# KNoT_Thing_Starter2_Board.net
KiCad netlist of a schematic drawn in Altium Designer
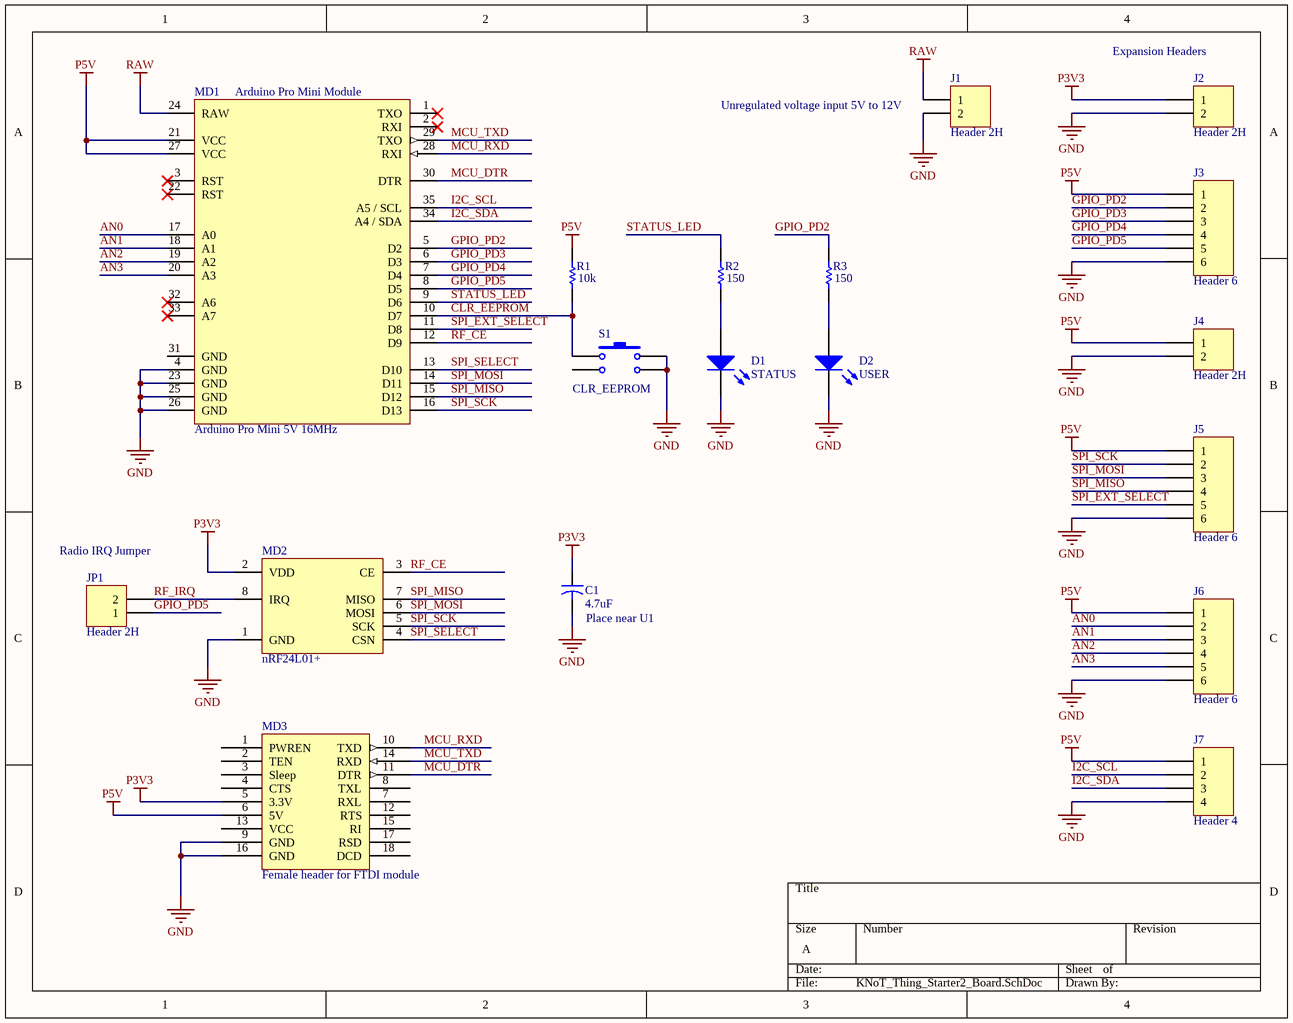
[diagram p0: KNoT_Thing_Starter2_Board.SchDoc]

(export (version "E")
  (design (tool "Eeschema 10.0.6"))
  (components
    (comp (ref "C1")
      (value "4.7uF")
      (footprint "CAP RADIAL 5mm")
      (description "Capacitor Radial 4.7µF")
      (fields (field (name "Comment") "CAPC_RADIAL_100") (field (name "PUBLISHER") "Altium Limited"))
      (libsource (lib "KNoT_Thing") (part "CAPC1608L_1"))
    )
    (comp (ref "D1")
      (value "STATUS")
      (footprint "LED")
      (description "Typical RED, GREEN, YELLOW, AMBER GaAs LED")
      (fields (field (name "PUBLISHER") "Altium Limited"))
      (libsource (lib "KNoT_Thing") (part "LED"))
    )
    (comp (ref "D2")
      (value "USER")
      (footprint "LED")
      (description "Typical RED, GREEN, YELLOW, AMBER GaAs LED")
      (fields (field (name "PUBLISHER") "Altium Limited"))
      (libsource (lib "KNoT_Thing") (part "LED"))
    )
    (comp (ref "J1")
      (value "Header 2H")
      (footprint "HDR1X2")
      (description "Header, 2-Pin, Right Angle")
      (fields (field (name "PUBLISHER") "Altium Limited"))
      (libsource (lib "KNoT_Thing") (part "Header 2H"))
    )
    (comp (ref "J2")
      (value "Header 2H")
      (footprint "HDR1X2")
      (description "Header, 2-Pin, Right Angle")
      (fields (field (name "PUBLISHER") "Altium Limited"))
      (libsource (lib "KNoT_Thing") (part "Header 2H"))
    )
    (comp (ref "J3")
      (value "Header 6")
      (footprint "HDR1X6")
      (description "Header, 6-Pin")
      (fields (field (name "PUBLISHER") "Altium Limited"))
      (libsource (lib "KNoT_Thing") (part "Header 6"))
    )
    (comp (ref "J4")
      (value "Header 2H")
      (footprint "HDR1X2")
      (description "Header, 2-Pin, Right Angle")
      (fields (field (name "PUBLISHER") "Altium Limited"))
      (libsource (lib "KNoT_Thing") (part "Header 2H"))
    )
    (comp (ref "J5")
      (value "Header 6")
      (footprint "HDR1X6")
      (description "Header, 6-Pin")
      (fields (field (name "PUBLISHER") "Altium Limited"))
      (libsource (lib "KNoT_Thing") (part "Header 6"))
    )
    (comp (ref "J6")
      (value "Header 6")
      (footprint "HDR1X6")
      (description "Header, 6-Pin")
      (fields (field (name "PUBLISHER") "Altium Limited"))
      (libsource (lib "KNoT_Thing") (part "Header 6"))
    )
    (comp (ref "J7")
      (value "Header 4")
      (footprint "HDR1X4")
      (description "Header, 4-Pin")
      (fields (field (name "PUBLISHER") "Altium Limited"))
      (libsource (lib "KNoT_Thing") (part "Header 4"))
    )
    (comp (ref "JP1")
      (value "Header 2H")
      (footprint "HDR1X2")
      (description "Header, 2-Pin, Right Angle")
      (fields (field (name "PUBLISHER") "Altium Limited"))
      (libsource (lib "") (part "Header 2H_1"))
    )
    (comp (ref "MD1")
      (value "Arduino Pro Mini 5V 16MHz")
      (footprint "Arduino Pro Mini")
      (libsource (lib "KNoT_Thing") (part "Arduino Pro Mini 5V 16MHz"))
    )
    (comp (ref "MD2")
      (value "nRF24L01+")
      (footprint "nRF24L01+ Module")
      (description "2x4 Female Header Conector")
      (libsource (lib "KNoT_Thing") (part "nRF24L01+ Module"))
    )
    (comp (ref "MD3")
      (value "Female header for FTDI module")
      (footprint "FTDI_Module")
      (description "Connection header for custom FTDI module")
      (libsource (lib "KNoT_Thing") (part "Module_FTDI"))
    )
    (comp (ref "R1")
      (value "10k")
      (footprint "AXIAL-3mm")
      (description "Resistor")
      (fields (field (name "Comment") "Res1") (field (name "PUBLISHER") "Altium Limited"))
      (libsource (lib "KNoT_Thing") (part "Res1"))
    )
    (comp (ref "R2")
      (value "150")
      (footprint "AXIAL-3mm")
      (description "Resistor")
      (fields (field (name "Comment") "Res1") (field (name "PUBLISHER") "Altium Limited"))
      (libsource (lib "KNoT_Thing") (part "Res1"))
    )
    (comp (ref "R3")
      (value "150")
      (footprint "AXIAL-3mm")
      (description "Resistor")
      (fields (field (name "Comment") "Res1") (field (name "PUBLISHER") "Altium Limited"))
      (libsource (lib "KNoT_Thing") (part "Res1"))
    )
    (comp (ref "S1")
      (value "CLR_EEPROM")
      (footprint "SW-TACT")
      (description "B3F-1002 SWITCH TACT 6MM MOM 150GF")
      (fields (field (name "PUBLISHER") "Altium Limited"))
      (libsource (lib "KNoT_Thing") (part "SW-PB"))
    )
  )
  (nets
    (net (code "1") (name "/AN0") (class "Default")
      (node (ref "J6") (pin "2") (pinfunction "2_2") (pintype "passive"))
      (node (ref "MD1") (pin "17") (pinfunction "A0_17") (pintype "passive"))
    )
    (net (code "2") (name "/AN1") (class "Default")
      (node (ref "J6") (pin "3") (pinfunction "3_3") (pintype "passive"))
      (node (ref "MD1") (pin "18") (pinfunction "A1_18") (pintype "passive"))
    )
    (net (code "3") (name "/AN2") (class "Default")
      (node (ref "J6") (pin "4") (pinfunction "4_4") (pintype "passive"))
      (node (ref "MD1") (pin "19") (pinfunction "A2_19") (pintype "passive"))
    )
    (net (code "4") (name "/AN3") (class "Default")
      (node (ref "J6") (pin "5") (pinfunction "5_5") (pintype "passive"))
      (node (ref "MD1") (pin "20") (pinfunction "A3_20") (pintype "passive"))
    )
    (net (code "5") (name "/CLR_EEPROM") (class "Default")
      (node (ref "MD1") (pin "10") (pinfunction "D7_10") (pintype "passive"))
      (node (ref "R1") (pin "2") (pinfunction "2_2") (pintype "passive"))
      (node (ref "S1") (pin "1") (pinfunction "1_1") (pintype "passive"))
    )
    (net (code "6") (name "/GPIO_PD2") (class "Default")
      (node (ref "J3") (pin "2") (pinfunction "2_2") (pintype "passive"))
      (node (ref "MD1") (pin "5") (pinfunction "D2_5") (pintype "passive"))
      (node (ref "R3") (pin "1") (pinfunction "1_1") (pintype "passive"))
    )
    (net (code "7") (name "/GPIO_PD3") (class "Default")
      (node (ref "J3") (pin "3") (pinfunction "3_3") (pintype "passive"))
      (node (ref "MD1") (pin "6") (pinfunction "D3_6") (pintype "passive"))
    )
    (net (code "8") (name "/GPIO_PD4") (class "Default")
      (node (ref "J3") (pin "4") (pinfunction "4_4") (pintype "passive"))
      (node (ref "MD1") (pin "7") (pinfunction "D4_7") (pintype "passive"))
    )
    (net (code "9") (name "/GPIO_PD5") (class "Default")
      (node (ref "J3") (pin "5") (pinfunction "5_5") (pintype "passive"))
      (node (ref "JP1") (pin "1") (pinfunction "1_1") (pintype "passive"))
      (node (ref "MD1") (pin "8") (pinfunction "D5_8") (pintype "passive"))
    )
    (net (code "10") (name "/I2C_SCL") (class "Default")
      (node (ref "J7") (pin "2") (pinfunction "2_2") (pintype "passive"))
      (node (ref "MD1") (pin "35") (pinfunction "A5_/_SCL_35") (pintype "passive"))
    )
    (net (code "11") (name "/I2C_SDA") (class "Default")
      (node (ref "J7") (pin "3") (pinfunction "3_3") (pintype "passive"))
      (node (ref "MD1") (pin "34") (pinfunction "A4_/_SDA_34") (pintype "passive"))
    )
    (net (code "12") (name "/MCU_DTR") (class "Default")
      (node (ref "MD1") (pin "30") (pinfunction "DTR_30") (pintype "passive"))
      (node (ref "MD3") (pin "11") (pinfunction "DTR_11") (pintype "output"))
    )
    (net (code "13") (name "/MCU_RXD") (class "Default")
      (node (ref "MD1") (pin "28") (pinfunction "RXI_28") (pintype "input"))
      (node (ref "MD3") (pin "10") (pinfunction "TXD_10") (pintype "output"))
    )
    (net (code "14") (name "/MCU_TXD") (class "Default")
      (node (ref "MD1") (pin "29") (pinfunction "TXO_29") (pintype "output"))
      (node (ref "MD3") (pin "14") (pinfunction "RXD_14") (pintype "input"))
    )
    (net (code "15") (name "/RF_CE") (class "Default")
      (node (ref "MD1") (pin "12") (pinfunction "D9_12") (pintype "passive"))
      (node (ref "MD2") (pin "3") (pinfunction "CE_3") (pintype "passive"))
    )
    (net (code "16") (name "/RF_IRQ") (class "Default")
      (node (ref "JP1") (pin "2") (pinfunction "2_2") (pintype "passive"))
      (node (ref "MD2") (pin "8") (pinfunction "IRQ_8") (pintype "passive"))
    )
    (net (code "17") (name "/SPI_EXT_SELECT") (class "Default")
      (node (ref "J5") (pin "5") (pinfunction "5_5") (pintype "passive"))
      (node (ref "MD1") (pin "11") (pinfunction "D8_11") (pintype "passive"))
    )
    (net (code "18") (name "/SPI_MISO") (class "Default")
      (node (ref "J5") (pin "4") (pinfunction "4_4") (pintype "passive"))
      (node (ref "MD1") (pin "15") (pinfunction "D12_15") (pintype "passive"))
      (node (ref "MD2") (pin "7") (pinfunction "MISO_7") (pintype "passive"))
    )
    (net (code "19") (name "/SPI_MOSI") (class "Default")
      (node (ref "J5") (pin "3") (pinfunction "3_3") (pintype "passive"))
      (node (ref "MD1") (pin "14") (pinfunction "D11_14") (pintype "passive"))
      (node (ref "MD2") (pin "6") (pinfunction "MOSI_6") (pintype "passive"))
    )
    (net (code "20") (name "/SPI_SCK") (class "Default")
      (node (ref "J5") (pin "2") (pinfunction "2_2") (pintype "passive"))
      (node (ref "MD1") (pin "16") (pinfunction "D13_16") (pintype "passive"))
      (node (ref "MD2") (pin "5") (pinfunction "SCK_5") (pintype "passive"))
    )
    (net (code "21") (name "/SPI_SELECT") (class "Default")
      (node (ref "MD1") (pin "13") (pinfunction "D10_13") (pintype "passive"))
      (node (ref "MD2") (pin "4") (pinfunction "CSN_4") (pintype "passive"))
    )
    (net (code "22") (name "/STATUS_LED") (class "Default")
      (node (ref "MD1") (pin "9") (pinfunction "D6_9") (pintype "passive"))
      (node (ref "R2") (pin "1") (pinfunction "1_1") (pintype "passive"))
    )
    (net (code "23") (name "GND") (class "Default")
      (node (ref "C1") (pin "2") (pinfunction "2_2") (pintype "passive"))
      (node (ref "D1") (pin "2") (pinfunction "K_2") (pintype "passive"))
      (node (ref "D2") (pin "2") (pinfunction "K_2") (pintype "passive"))
      (node (ref "J1") (pin "2") (pinfunction "2_2") (pintype "passive"))
      (node (ref "J2") (pin "2") (pinfunction "2_2") (pintype "passive"))
      (node (ref "J3") (pin "6") (pinfunction "6_6") (pintype "passive"))
      (node (ref "J4") (pin "2") (pinfunction "2_2") (pintype "passive"))
      (node (ref "J5") (pin "6") (pinfunction "6_6") (pintype "passive"))
      (node (ref "J6") (pin "6") (pinfunction "6_6") (pintype "passive"))
      (node (ref "J7") (pin "4") (pinfunction "4_4") (pintype "passive"))
      (node (ref "MD1") (pin "23") (pinfunction "GND_23") (pintype "passive"))
      (node (ref "MD1") (pin "25") (pinfunction "GND_25") (pintype "passive"))
      (node (ref "MD1") (pin "26") (pinfunction "GND_26") (pintype "passive"))
      (node (ref "MD1") (pin "4") (pinfunction "GND_4") (pintype "passive"))
      (node (ref "MD2") (pin "1") (pinfunction "GND_1") (pintype "passive"))
      (node (ref "MD3") (pin "16") (pinfunction "GND_16") (pintype "passive"))
      (node (ref "MD3") (pin "9") (pinfunction "GND_9") (pintype "passive"))
      (node (ref "S1") (pin "3") (pinfunction "3_3") (pintype "passive"))
      (node (ref "S1") (pin "4") (pinfunction "4_4") (pintype "passive"))
    )
    (net (code "24") (name "Net-(D1-A)") (class "Default")
      (node (ref "D1") (pin "1") (pinfunction "A_1") (pintype "passive"))
      (node (ref "R2") (pin "2") (pinfunction "2_2") (pintype "passive"))
    )
    (net (code "25") (name "Net-(D2-A)") (class "Default")
      (node (ref "D2") (pin "1") (pinfunction "A_1") (pintype "passive"))
      (node (ref "R3") (pin "2") (pinfunction "2_2") (pintype "passive"))
    )
    (net (code "26") (name "P3V3") (class "Default")
      (node (ref "C1") (pin "1") (pinfunction "1_1") (pintype "passive"))
      (node (ref "J2") (pin "1") (pinfunction "1_1") (pintype "passive"))
      (node (ref "MD2") (pin "2") (pinfunction "VDD_2") (pintype "passive"))
      (node (ref "MD3") (pin "5") (pinfunction "3.3V_5") (pintype "passive"))
    )
    (net (code "27") (name "P5V") (class "Default")
      (node (ref "J3") (pin "1") (pinfunction "1_1") (pintype "passive"))
      (node (ref "J4") (pin "1") (pinfunction "1_1") (pintype "passive"))
      (node (ref "J5") (pin "1") (pinfunction "1_1") (pintype "passive"))
      (node (ref "J6") (pin "1") (pinfunction "1_1") (pintype "passive"))
      (node (ref "J7") (pin "1") (pinfunction "1_1") (pintype "passive"))
      (node (ref "MD1") (pin "21") (pinfunction "VCC_21") (pintype "passive"))
      (node (ref "MD1") (pin "27") (pinfunction "VCC_27") (pintype "passive"))
      (node (ref "MD3") (pin "6") (pinfunction "5V_6") (pintype "passive"))
      (node (ref "R1") (pin "1") (pinfunction "1_1") (pintype "passive"))
    )
    (net (code "28") (name "RAW") (class "Default")
      (node (ref "J1") (pin "1") (pinfunction "1_1") (pintype "passive"))
      (node (ref "MD1") (pin "24") (pinfunction "RAW_24") (pintype "passive"))
    )
    (net (code "29") (name "unconnected-(MD1-A6-Pad32)") (class "Default")
      (node (ref "MD1") (pin "32") (pinfunction "A6_32") (pintype "passive+no_connect"))
    )
    (net (code "30") (name "unconnected-(MD1-A7-Pad33)") (class "Default")
      (node (ref "MD1") (pin "33") (pinfunction "A7_33") (pintype "passive+no_connect"))
    )
    (net (code "31") (name "unconnected-(MD1-GND-Pad31)") (class "Default")
      (node (ref "MD1") (pin "31") (pinfunction "GND_31") (pintype "passive"))
    )
    (net (code "32") (name "unconnected-(MD1-RST-Pad3)") (class "Default")
      (node (ref "MD1") (pin "3") (pinfunction "RST_3") (pintype "passive+no_connect"))
    )
    (net (code "33") (name "unconnected-(MD1-RST-Pad22)") (class "Default")
      (node (ref "MD1") (pin "22") (pinfunction "RST_22") (pintype "passive+no_connect"))
    )
    (net (code "34") (name "unconnected-(MD1-RXI-Pad2)") (class "Default")
      (node (ref "MD1") (pin "2") (pinfunction "RXI_2") (pintype "passive+no_connect"))
    )
    (net (code "35") (name "unconnected-(MD1-TXO-Pad1)") (class "Default")
      (node (ref "MD1") (pin "1") (pinfunction "TXO_1") (pintype "passive+no_connect"))
    )
    (net (code "36") (name "unconnected-(MD3-CTS-Pad4)") (class "Default")
      (node (ref "MD3") (pin "4") (pinfunction "CTS_4") (pintype "passive"))
    )
    (net (code "37") (name "unconnected-(MD3-DCD-Pad18)") (class "Default")
      (node (ref "MD3") (pin "18") (pinfunction "DCD_18") (pintype "passive"))
    )
    (net (code "38") (name "unconnected-(MD3-PWREN-Pad1)") (class "Default")
      (node (ref "MD3") (pin "1") (pinfunction "PWREN_1") (pintype "passive"))
    )
    (net (code "39") (name "unconnected-(MD3-RI-Pad15)") (class "Default")
      (node (ref "MD3") (pin "15") (pinfunction "RI_15") (pintype "passive"))
    )
    (net (code "40") (name "unconnected-(MD3-RSD-Pad17)") (class "Default")
      (node (ref "MD3") (pin "17") (pinfunction "RSD_17") (pintype "passive"))
    )
    (net (code "41") (name "unconnected-(MD3-RTS-Pad12)") (class "Default")
      (node (ref "MD3") (pin "12") (pinfunction "RTS_12") (pintype "passive"))
    )
    (net (code "42") (name "unconnected-(MD3-RXL-Pad7)") (class "Default")
      (node (ref "MD3") (pin "7") (pinfunction "RXL_7") (pintype "passive"))
    )
    (net (code "43") (name "unconnected-(MD3-Sleep-Pad3)") (class "Default")
      (node (ref "MD3") (pin "3") (pinfunction "Sleep_3") (pintype "passive"))
    )
    (net (code "44") (name "unconnected-(MD3-TEN-Pad2)") (class "Default")
      (node (ref "MD3") (pin "2") (pinfunction "TEN_2") (pintype "passive"))
    )
    (net (code "45") (name "unconnected-(MD3-TXL-Pad8)") (class "Default")
      (node (ref "MD3") (pin "8") (pinfunction "TXL_8") (pintype "passive"))
    )
    (net (code "46") (name "unconnected-(MD3-VCC-Pad13)") (class "Default")
      (node (ref "MD3") (pin "13") (pinfunction "VCC_13") (pintype "passive"))
    )
    (net (code "47") (name "unconnected-(S1-Pad2)") (class "Default")
      (node (ref "S1") (pin "2") (pinfunction "2_2") (pintype "passive"))
    )
  )
)
